# BrahMos_ESP8266.net
KiCad netlist of a schematic drawn in Altium Designer
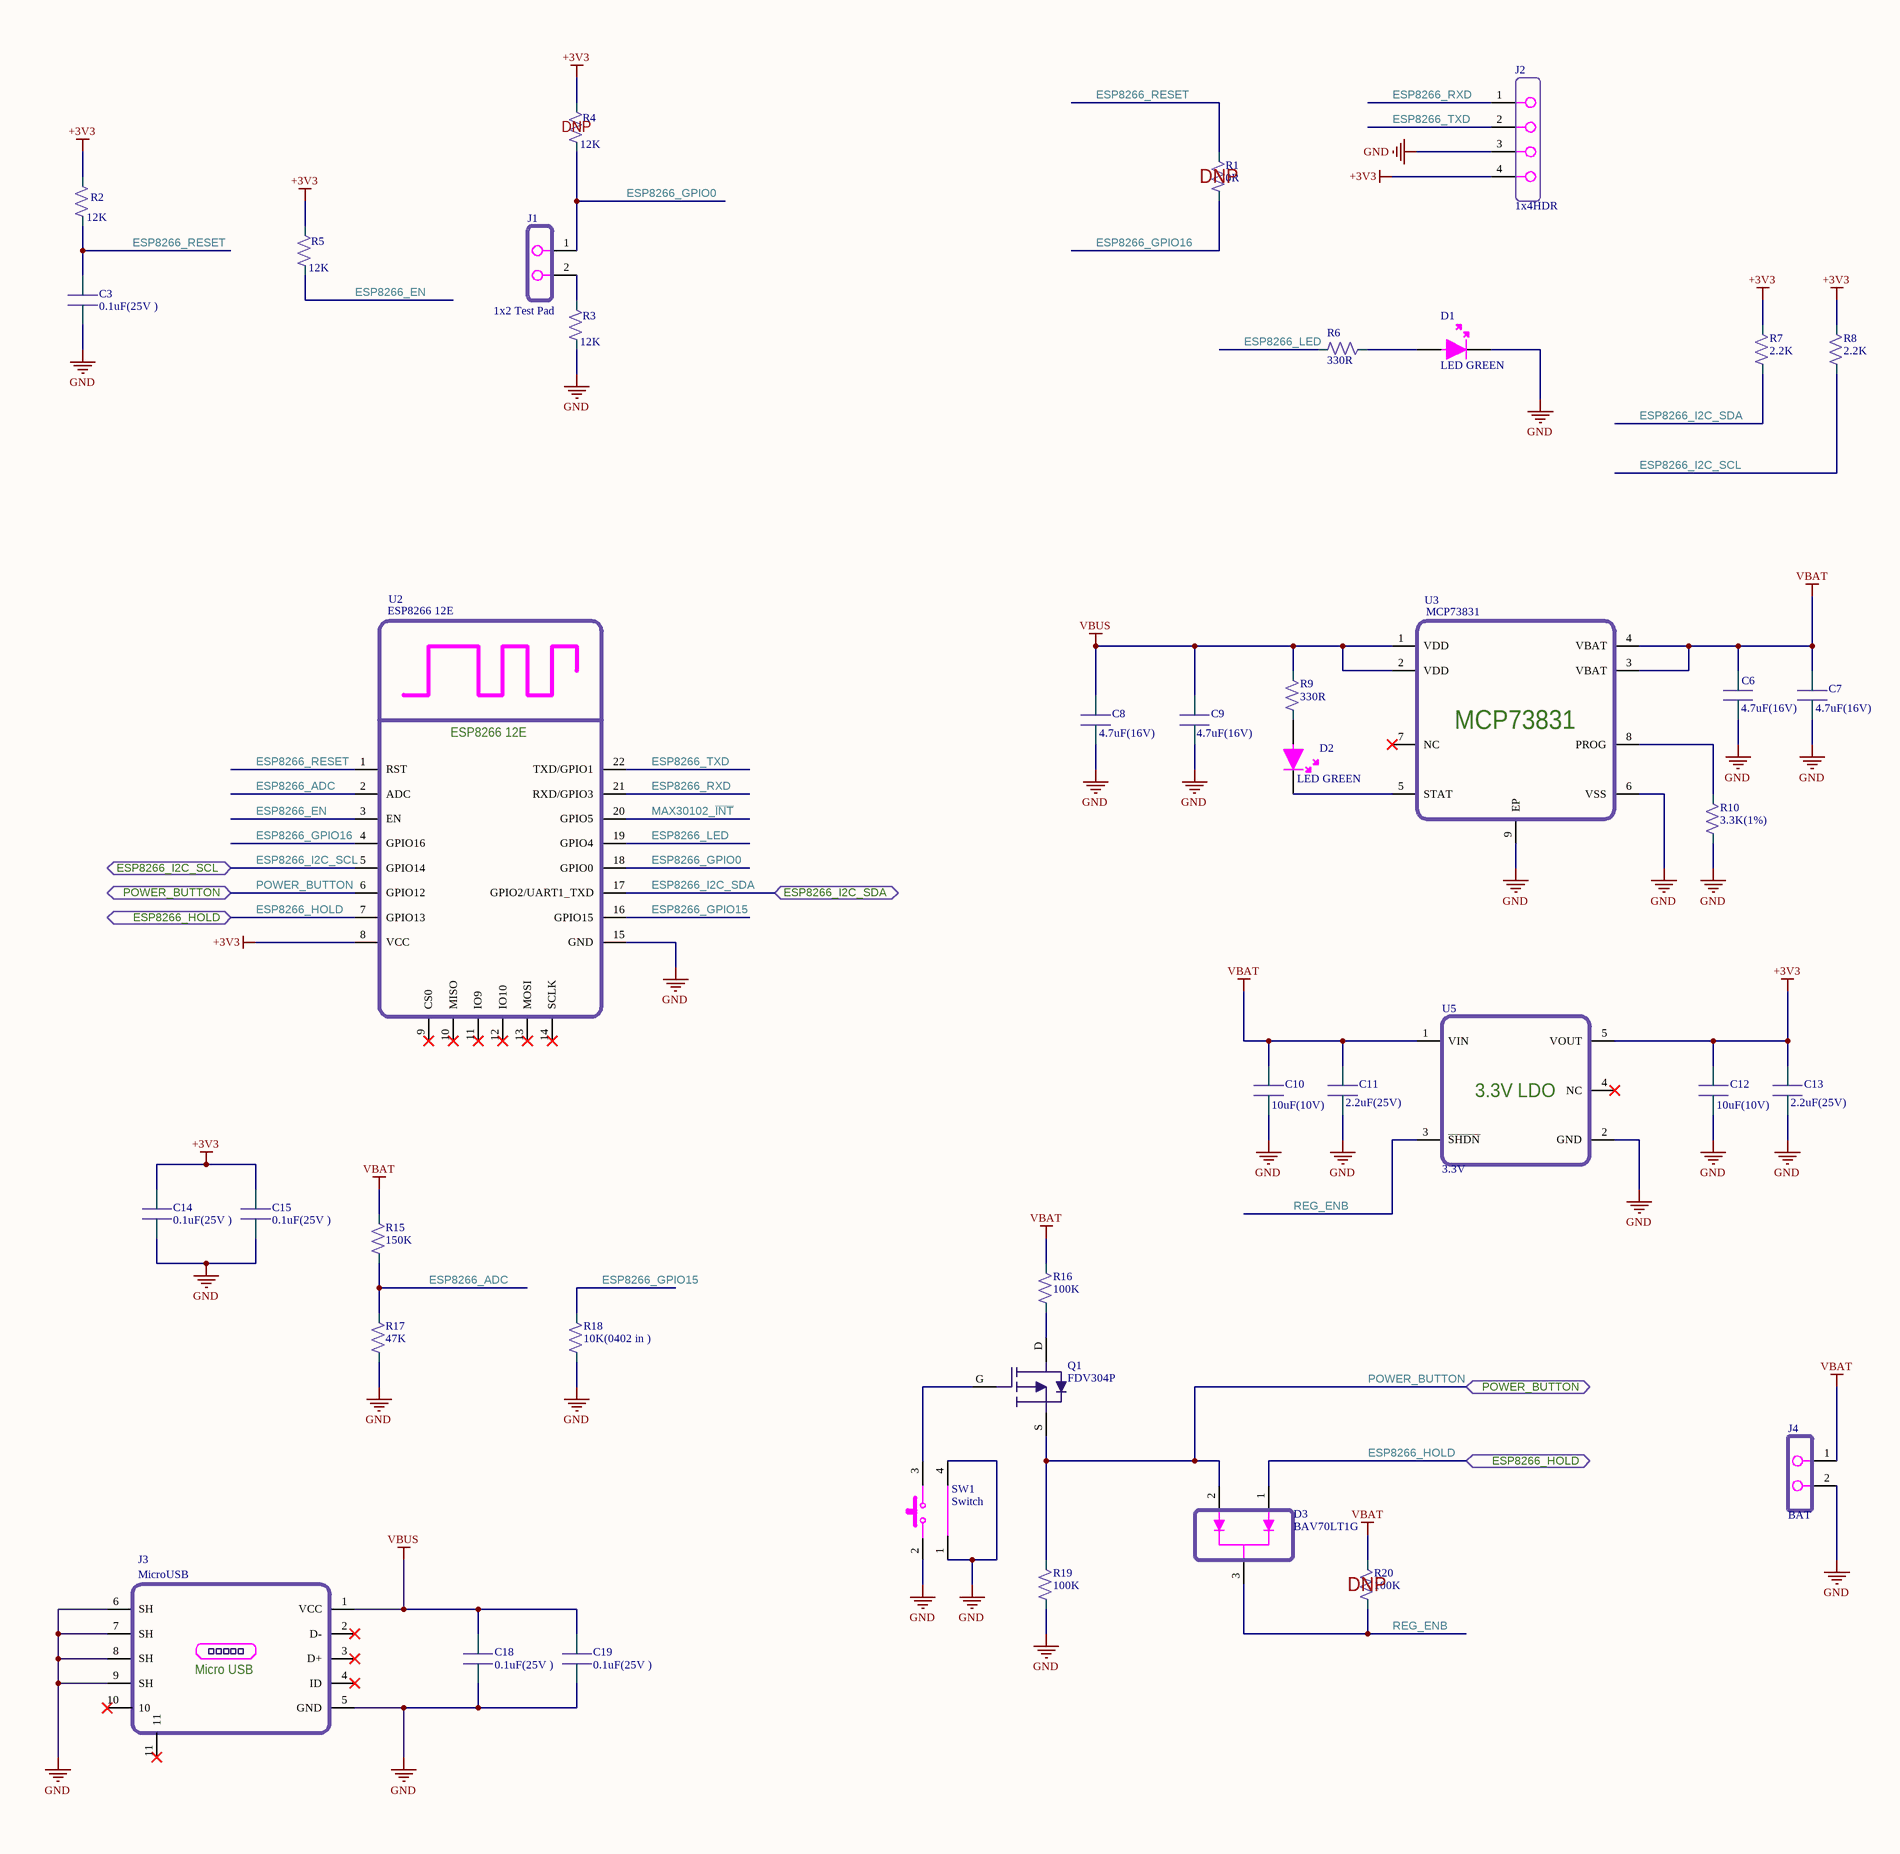
[diagram p0: BrahMos_ESP8266.SchDoc, left]
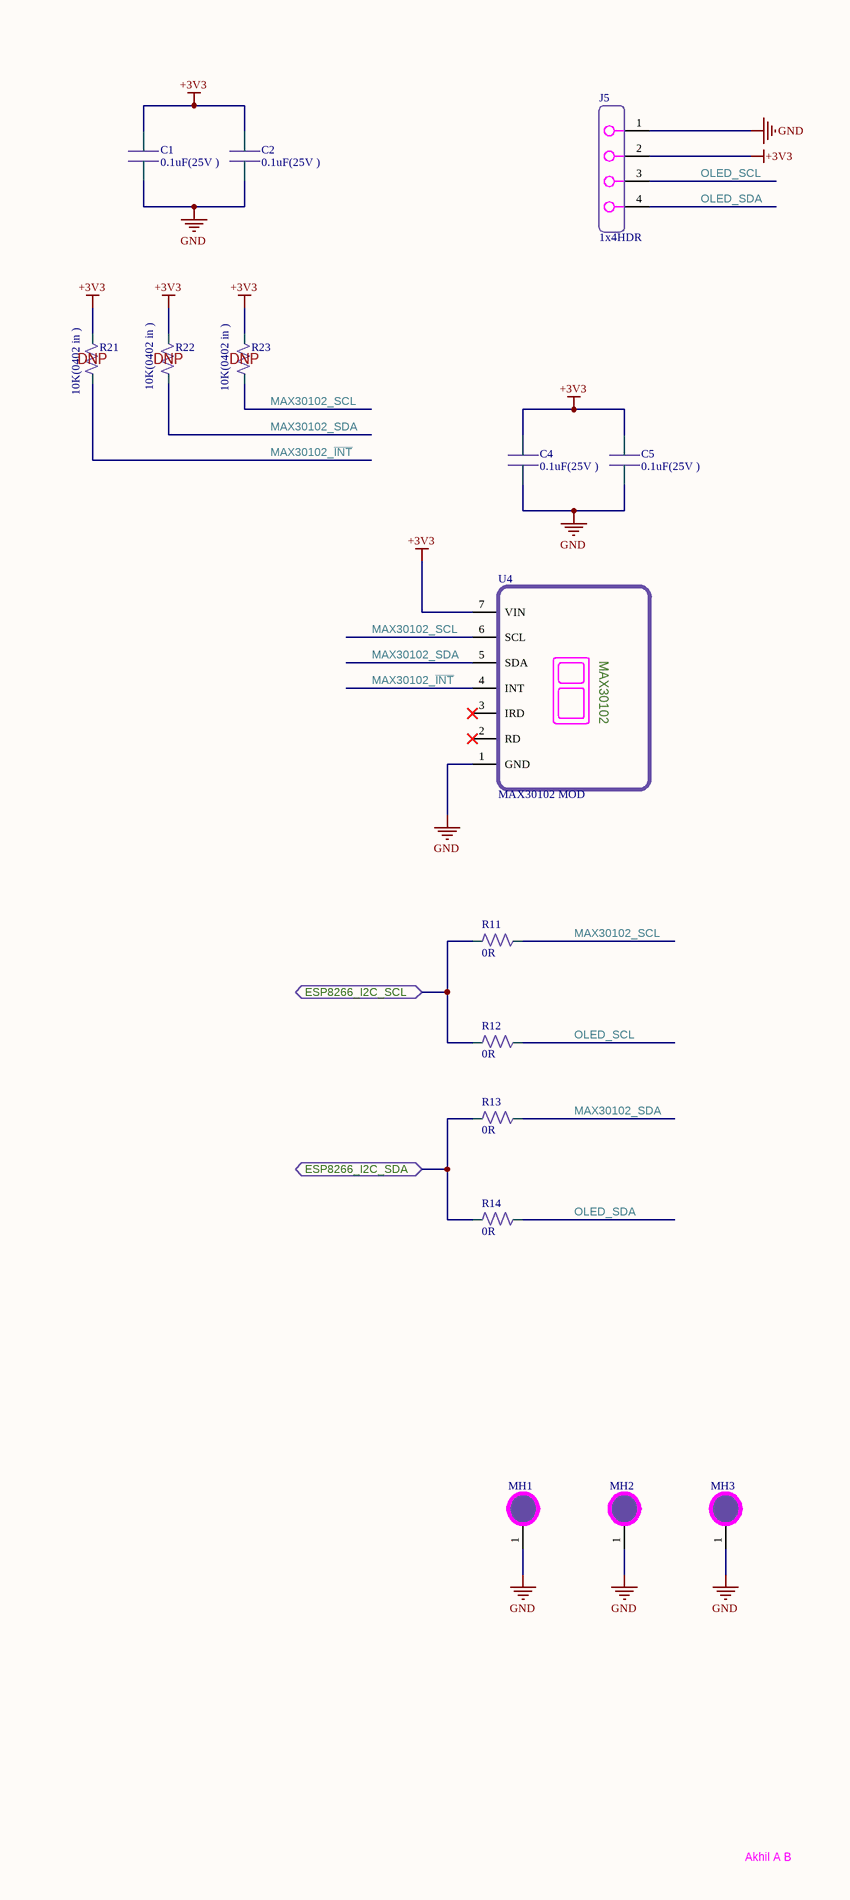
[diagram p1: BrahMos_ESP8266.SchDoc, right]

(export (version "E")
  (design (tool "Eeschema 10.0.6"))
  (components
    (comp (ref "C1")
      (value "0.1uF(25V )")
      (footprint "CAPACITOR_0402")
      (description "0.1µF ±10% 25V Ceramic Capacitor X7R 0402 (1005 Metric)")
      (fields
        (field (name "MANUFACTURERPARTNUMBER") "GRM155R71E104KE14J")
        (field (name "MANUFACTURER") "Murata Electronics")
      )
      (libsource (lib "Capacitors") (part "GRM155R71E104KE14J"))
    )
    (comp (ref "C2")
      (value "0.1uF(25V )")
      (footprint "CAPACITOR_0402")
      (description "0.1µF ±10% 25V Ceramic Capacitor X7R 0402 (1005 Metric)")
      (fields
        (field (name "MANUFACTURERPARTNUMBER") "GRM155R71E104KE14J")
        (field (name "MANUFACTURER") "Murata Electronics")
      )
      (libsource (lib "Capacitors") (part "GRM155R71E104KE14J"))
    )
    (comp (ref "C3")
      (value "0.1uF(25V )")
      (footprint "CAPACITOR_0402")
      (description "0.1µF ±10% 25V Ceramic Capacitor X7R 0402 (1005 Metric)")
      (fields
        (field (name "MANUFACTURERPARTNUMBER") "GRM155R71E104KE14J")
        (field (name "MANUFACTURER") "Murata Electronics")
      )
      (libsource (lib "Capacitors") (part "GRM155R71E104KE14J"))
    )
    (comp (ref "C4")
      (value "0.1uF(25V )")
      (footprint "CAPACITOR_0402")
      (description "0.1µF ±10% 25V Ceramic Capacitor X7R 0402 (1005 Metric)")
      (fields
        (field (name "MANUFACTURERPARTNUMBER") "GRM155R71E104KE14J")
        (field (name "MANUFACTURER") "Murata Electronics")
      )
      (libsource (lib "Capacitors") (part "GRM155R71E104KE14J"))
    )
    (comp (ref "C5")
      (value "0.1uF(25V )")
      (footprint "CAPACITOR_0402")
      (description "0.1µF ±10% 25V Ceramic Capacitor X7R 0402 (1005 Metric)")
      (fields
        (field (name "MANUFACTURERPARTNUMBER") "GRM155R71E104KE14J")
        (field (name "MANUFACTURER") "Murata Electronics")
      )
      (libsource (lib "Capacitors") (part "GRM155R71E104KE14J"))
    )
    (comp (ref "C6")
      (value "4.7uF(16V)")
      (footprint "CAPACITOR_0402")
      (description "4.7µF ±20% 16V Ceramic Capacitor X5R 0402 (1005 Metric)")
      (fields
        (field (name "MANUFACTURERPARTNUMBER") "0402YD475MAT2A")
        (field (name "MANUFACTURER") "AVX Corporation")
      )
      (libsource (lib "Capacitors") (part "0402YD475MAT2A"))
    )
    (comp (ref "C7")
      (value "4.7uF(16V)")
      (footprint "CAPACITOR_0402")
      (description "4.7µF ±20% 16V Ceramic Capacitor X5R 0402 (1005 Metric)")
      (fields
        (field (name "MANUFACTURERPARTNUMBER") "0402YD475MAT2A")
        (field (name "MANUFACTURER") "AVX Corporation")
      )
      (libsource (lib "Capacitors") (part "0402YD475MAT2A"))
    )
    (comp (ref "C8")
      (value "4.7uF(16V)")
      (footprint "CAPACITOR_0402")
      (description "4.7µF ±20% 16V Ceramic Capacitor X5R 0402 (1005 Metric)")
      (fields
        (field (name "MANUFACTURERPARTNUMBER") "0402YD475MAT2A")
        (field (name "MANUFACTURER") "AVX Corporation")
      )
      (libsource (lib "Capacitors") (part "0402YD475MAT2A"))
    )
    (comp (ref "C9")
      (value "4.7uF(16V)")
      (footprint "CAPACITOR_0402")
      (description "4.7µF ±20% 16V Ceramic Capacitor X5R 0402 (1005 Metric)")
      (fields
        (field (name "MANUFACTURERPARTNUMBER") "0402YD475MAT2A")
        (field (name "MANUFACTURER") "AVX Corporation")
      )
      (libsource (lib "Capacitors") (part "0402YD475MAT2A"))
    )
    (comp (ref "C10")
      (value "10uF(10V)")
      (footprint "CAPACITOR_0402")
      (description "10µF ±20% 10V Ceramic Capacitor X5R 0402 (1005 Metric)")
      (fields
        (field (name "MANUFACTURERPARTNUMBER") "CL05A106MP8NUB8")
        (field (name "MANUFACTURER") "Samsung Electro-Mechanics")
      )
      (libsource (lib "Capacitors") (part "CL05A106MP8NUB8"))
    )
    (comp (ref "C11")
      (value "2.2uF(25V)")
      (footprint "CAPACITOR_0402")
      (description "2.2 µF ±10% 25V Ceramic Capacitor X5R 0402 (1005 Metric)")
      (fields
        (field (name "MANUAFCTURERPARTNUMBER") "GRT155R61E225KE13D")
        (field (name "MANUFACTURER") "Murata Electronics")
      )
      (libsource (lib "Capacitors") (part "GRT155R61E225KE13D"))
    )
    (comp (ref "C12")
      (value "10uF(10V)")
      (footprint "CAPACITOR_0402")
      (description "10µF ±20% 10V Ceramic Capacitor X5R 0402 (1005 Metric)")
      (fields
        (field (name "MANUFACTURERPARTNUMBER") "CL05A106MP8NUB8")
        (field (name "MANUFACTURER") "Samsung Electro-Mechanics")
      )
      (libsource (lib "Capacitors") (part "CL05A106MP8NUB8"))
    )
    (comp (ref "C13")
      (value "2.2uF(25V)")
      (footprint "CAPACITOR_0402")
      (description "2.2 µF ±10% 25V Ceramic Capacitor X5R 0402 (1005 Metric)")
      (fields
        (field (name "MANUAFCTURERPARTNUMBER") "GRT155R61E225KE13D")
        (field (name "MANUFACTURER") "Murata Electronics")
      )
      (libsource (lib "Capacitors") (part "GRT155R61E225KE13D"))
    )
    (comp (ref "C14")
      (value "0.1uF(25V )")
      (footprint "CAPACITOR_0402")
      (description "0.1µF ±10% 25V Ceramic Capacitor X7R 0402 (1005 Metric)")
      (fields
        (field (name "MANUFACTURERPARTNUMBER") "GRM155R71E104KE14J")
        (field (name "MANUFACTURER") "Murata Electronics")
      )
      (libsource (lib "Capacitors") (part "GRM155R71E104KE14J"))
    )
    (comp (ref "C15")
      (value "0.1uF(25V )")
      (footprint "CAPACITOR_0402")
      (description "0.1µF ±10% 25V Ceramic Capacitor X7R 0402 (1005 Metric)")
      (fields
        (field (name "MANUFACTURERPARTNUMBER") "GRM155R71E104KE14J")
        (field (name "MANUFACTURER") "Murata Electronics")
      )
      (libsource (lib "Capacitors") (part "GRM155R71E104KE14J"))
    )
    (comp (ref "C18")
      (value "0.1uF(25V )")
      (footprint "CAPACITOR_0402")
      (description "0.1µF ±10% 25V Ceramic Capacitor X7R 0402 (1005 Metric)")
      (fields
        (field (name "MANUFACTURERPARTNUMBER") "GRM155R71E104KE14J")
        (field (name "MANUFACTURER") "Murata Electronics")
      )
      (libsource (lib "Capacitors") (part "GRM155R71E104KE14J"))
    )
    (comp (ref "C19")
      (value "0.1uF(25V )")
      (footprint "CAPACITOR_0402")
      (description "0.1µF ±10% 25V Ceramic Capacitor X7R 0402 (1005 Metric)")
      (fields
        (field (name "MANUFACTURERPARTNUMBER") "GRM155R71E104KE14J")
        (field (name "MANUFACTURER") "Murata Electronics")
      )
      (libsource (lib "Capacitors") (part "GRM155R71E104KE14J"))
    )
    (comp (ref "D1")
      (value "LED GREEN")
      (footprint "0603_LED")
      (description "Green 570nm LED Indication - Discrete 2.1V 0603 (1608 Metric)")
      (fields (field (name "MANUFACTURER PART NUMBER") "XZVG53W-8"))
      (libsource (lib "Diodes") (part "XZVG53W-8"))
    )
    (comp (ref "D2")
      (value "LED GREEN")
      (footprint "0603_LED")
      (description "Green 570nm LED Indication - Discrete 2.1V 0603 (1608 Metric)")
      (fields (field (name "MANUFACTURER PART NUMBER") "XZVG53W-8"))
      (libsource (lib "Diodes") (part "XZVG53W-8"))
    )
    (comp (ref "D3")
      (value "BAV70LT1G")
      (footprint "SOT-23_3LEAD - BAV70")
      (description "Diode Array 1 Pair Common Cathode Standard 200mA (DC) Surface Mount TO-236-3, SC-59, SOT-23-3")
      (fields (field (name "MANUFACTURER") "ON Semiconductor"))
      (libsource (lib "Diodes") (part "BAV70LT1G"))
    )
    (comp (ref "J1")
      (value "1x2 Test Pad")
      (footprint "dual test pad 1.27")
      (libsource (lib "connectors") (part "1x2Test Pad"))
    )
    (comp (ref "J2")
      (value "1x4HDR")
      (footprint "P2.541X4HDR")
      (description "Connector Header Through Hole 4 position 0.100\" (2.54mm)")
      (fields (field (name "MANUFACTURERPARTNUMBER") "PEC04SAAN"))
      (libsource (lib "connectors") (part "PEC04SAAN"))
    )
    (comp (ref "J3")
      (value "MicroUSB")
      (footprint "Micro USB")
      (description "USB - micro B USB 2.0 Receptacle Connector 5 Position Surface Mount, Right Angle; Through Hole")
      (fields
        (field (name "MANUFACTURERPARTNUMBER") "629105150521")
        (field (name "MANUFACTURER") "Würth Elektronik")
      )
      (libsource (lib "Connectors") (part "629105150521"))
    )
    (comp (ref "J4")
      (value "BAT")
      (footprint "SM02B-SRSS-TB(LF)(SN)")
      (description "Connector Header Surface Mount, Right Angle 2 position 0.039\" (1.00mm)")
      (fields
        (field (name "MANUFACTURERPARTNUMBER") "SM02B-SRSS-TB(LF)(SN)")
        (field (name "MANUFACTURER") "JST Sales America Inc.")
      )
      (libsource (lib "connectors") (part "SM02B-SRSS-TB(LF)(SN)"))
    )
    (comp (ref "J5")
      (value "1x4HDR")
      (footprint "P2.541X4HDR")
      (description "Connector Header Through Hole 4 position 0.100\" (2.54mm)")
      (fields (field (name "MANUFACTURERPARTNUMBER") "PEC04SAAN"))
      (libsource (lib "connectors") (part "PEC04SAAN"))
    )
    (comp (ref "MH1")
      (value "Mounting Hole")
      (footprint "2mm mounting Hole")
      (description "2mm Mounting Hole")
      (libsource (lib "connectors") (part "2mm mounting hole"))
    )
    (comp (ref "MH2")
      (value "Mounting Hole")
      (footprint "2mm mounting Hole")
      (description "2mm Mounting Hole")
      (libsource (lib "connectors") (part "2mm mounting hole"))
    )
    (comp (ref "MH3")
      (value "Mounting Hole")
      (footprint "2mm mounting Hole")
      (description "2mm Mounting Hole")
      (libsource (lib "connectors") (part "2mm mounting hole"))
    )
    (comp (ref "Q1")
      (value "FDV304P")
      (footprint "SOT-23_3LEAD")
      (description "P-Channel 460mA (Ta) 350mW (Ta) Surface Mount SOT-23")
      (fields (field (name "MANUFACTURER") "ON Semiconductor"))
      (libsource (lib "Integrated Circuits") (part "FDV304P"))
    )
    (comp (ref "R1")
      (value "0R")
      (footprint "RESISTOR_0402")
      (fields
        (field (name "MANUFACTURERPARTNUMBER") "CR0402AJ/-000GAS")
        (field (name "MANUFACTURER") "Bourns Inc.")
      )
      (libsource (lib "Resistors") (part "CR0402AJ/-000GAS"))
    )
    (comp (ref "R2")
      (value "12K")
      (footprint "RESISTOR_0402")
      (description "±5% 0.1W, 1/10W Chip Resistor 0402 (1005 Metric) Automotive AEC-Q200 Thick Film")
      (fields
        (field (name "MANUFACTURERPARTNUMBER") "ERJ-2GEJ123X")
        (field (name "MANUFACTURER") "Panasonic Electronic Components")
      )
      (libsource (lib "Resistors") (part "ERJ-2GEJ123X"))
    )
    (comp (ref "R3")
      (value "12K")
      (footprint "RESISTOR_0402")
      (description "±5% 0.1W, 1/10W Chip Resistor 0402 (1005 Metric) Automotive AEC-Q200 Thick Film")
      (fields
        (field (name "MANUFACTURERPARTNUMBER") "ERJ-2GEJ123X")
        (field (name "MANUFACTURER") "Panasonic Electronic Components")
      )
      (libsource (lib "Resistors") (part "ERJ-2GEJ123X"))
    )
    (comp (ref "R4")
      (value "12K")
      (footprint "RESISTOR_0402")
      (description "±5% 0.1W, 1/10W Chip Resistor 0402 (1005 Metric) Automotive AEC-Q200 Thick Film")
      (fields
        (field (name "MANUFACTURERPARTNUMBER") "ERJ-2GEJ123X")
        (field (name "MANUFACTURER") "Panasonic Electronic Components")
      )
      (libsource (lib "Resistors") (part "ERJ-2GEJ123X"))
    )
    (comp (ref "R5")
      (value "12K")
      (footprint "RESISTOR_0402")
      (description "±5% 0.1W, 1/10W Chip Resistor 0402 (1005 Metric) Automotive AEC-Q200 Thick Film")
      (fields
        (field (name "MANUFACTURERPARTNUMBER") "ERJ-2GEJ123X")
        (field (name "MANUFACTURER") "Panasonic Electronic Components")
      )
      (libsource (lib "Resistors") (part "ERJ-2GEJ123X"))
    )
    (comp (ref "R6")
      (value "330R")
      (footprint "RESISTOR_0402")
      (fields
        (field (name "MANUFACTURERPARTNUMBER") "CRGCQ0603J330R")
        (field (name "MANUFACTURER") "TE Connectivity Passive Product")
      )
      (libsource (lib "Resistors") (part "CRGCQ0603J330R"))
    )
    (comp (ref "R7")
      (value "2.2K")
      (footprint "RESISTOR_0402")
      (description "2.2 kOhms ±5% 0.1W, 1/10W Chip Resistor 0402 (1005 Metric) Automotive AEC-Q200 Thick Film")
      (fields
        (field (name "MANUFACTURERPARTNUMBER") "ERJ-2GEJ222X")
        (field (name "MANUFACTURER") "Panasonic Electronic Components")
      )
      (libsource (lib "Resistors") (part "ERJ-2GEJ222X"))
    )
    (comp (ref "R8")
      (value "2.2K")
      (footprint "RESISTOR_0402")
      (description "2.2 kOhms ±5% 0.1W, 1/10W Chip Resistor 0402 (1005 Metric) Automotive AEC-Q200 Thick Film")
      (fields
        (field (name "MANUFACTURERPARTNUMBER") "ERJ-2GEJ222X")
        (field (name "MANUFACTURER") "Panasonic Electronic Components")
      )
      (libsource (lib "Resistors") (part "ERJ-2GEJ222X"))
    )
    (comp (ref "R9")
      (value "330R")
      (footprint "RESISTOR_0402")
      (fields
        (field (name "MANUFACTURERPARTNUMBER") "CRGCQ0603J330R")
        (field (name "MANUFACTURER") "TE Connectivity Passive Product")
      )
      (libsource (lib "Resistors") (part "CRGCQ0603J330R"))
    )
    (comp (ref "R10")
      (value "3.3K(1%)")
      (footprint "RESISTOR_0402")
      (fields
        (field (name "MANUFACTURERPARTNUMBER") "RK73H1ETTP3301F")
        (field (name "MANUFACTURER") "KOA Speer Electronics, Inc.")
      )
      (libsource (lib "Resistors") (part "RK73H1ETTP3301F"))
    )
    (comp (ref "R11")
      (value "0R")
      (footprint "RESISTOR_0402")
      (fields
        (field (name "MANUFACTURERPARTNUMBER") "CR0402AJ/-000GAS")
        (field (name "MANUFACTURER") "Bourns Inc.")
      )
      (libsource (lib "Resistors") (part "CR0402AJ/-000GAS"))
    )
    (comp (ref "R12")
      (value "0R")
      (footprint "RESISTOR_0402")
      (fields
        (field (name "MANUFACTURERPARTNUMBER") "CR0402AJ/-000GAS")
        (field (name "MANUFACTURER") "Bourns Inc.")
      )
      (libsource (lib "Resistors") (part "CR0402AJ/-000GAS"))
    )
    (comp (ref "R13")
      (value "0R")
      (footprint "RESISTOR_0402")
      (fields
        (field (name "MANUFACTURERPARTNUMBER") "CR0402AJ/-000GAS")
        (field (name "MANUFACTURER") "Bourns Inc.")
      )
      (libsource (lib "Resistors") (part "CR0402AJ/-000GAS"))
    )
    (comp (ref "R14")
      (value "0R")
      (footprint "RESISTOR_0402")
      (fields
        (field (name "MANUFACTURERPARTNUMBER") "CR0402AJ/-000GAS")
        (field (name "MANUFACTURER") "Bourns Inc.")
      )
      (libsource (lib "Resistors") (part "CR0402AJ/-000GAS"))
    )
    (comp (ref "R15")
      (value "150K")
      (footprint "RESISTOR_0402")
      (description "150 kOhms ±5% 0.1W, 1/10W Chip Resistor 0402 (1005 Metric) Automotive AEC-Q200 Thick Film")
      (fields
        (field (name "MANUFACTURERPARTNUMBER") "ERJ-2GEJ154X")
        (field (name "MANUFACTURER") "Panasonic Electronic Components")
      )
      (libsource (lib "Resistors") (part "ERJ-2GEJ154X"))
    )
    (comp (ref "R16")
      (value "100K")
      (footprint "RESISTOR_0402")
      (description "100 kOhms ±5% 0.1W, 1/10W Chip Resistor 0402 (1005 Metric) Automotive AEC-Q200 Thick Film")
      (fields
        (field (name "MANUFACTURERPARTNUMBER") "ERJ-2GEJ104X")
        (field (name "MANUFACTURER") "Panasonic Electronic Components")
      )
      (libsource (lib "Resistors") (part "ERJ-2GEJ104X"))
    )
    (comp (ref "R17")
      (value "47K")
      (footprint "RESISTOR_0402")
      (fields
        (field (name "MANUFACTURERPARTNUMBER") "ERJ-U02J473X")
        (field (name "MANUFACTURER") "Panasonic Electronic Components")
      )
      (libsource (lib "Resistors") (part "ERJ-U02J473X"))
    )
    (comp (ref "R18")
      (value "10K(0402 in )")
      (footprint "RESISTOR_0402")
      (fields
        (field (name "MANUFACTURERPARTNUMBER") "ERJ-U02J103X")
        (field (name "MANUFACTURER") "Panasonic Electronic Components")
      )
      (libsource (lib "Resistors") (part "ERJ-U02J103X"))
    )
    (comp (ref "R19")
      (value "100K")
      (footprint "RESISTOR_0402")
      (description "100 kOhms ±5% 0.1W, 1/10W Chip Resistor 0402 (1005 Metric) Automotive AEC-Q200 Thick Film")
      (fields
        (field (name "MANUFACTURERPARTNUMBER") "ERJ-2GEJ104X")
        (field (name "MANUFACTURER") "Panasonic Electronic Components")
      )
      (libsource (lib "Resistors") (part "ERJ-2GEJ104X"))
    )
    (comp (ref "R20")
      (value "100K")
      (footprint "RESISTOR_0402")
      (description "100 kOhms ±5% 0.1W, 1/10W Chip Resistor 0402 (1005 Metric) Automotive AEC-Q200 Thick Film")
      (fields
        (field (name "MANUFACTURERPARTNUMBER") "ERJ-2GEJ104X")
        (field (name "MANUFACTURER") "Panasonic Electronic Components")
      )
      (libsource (lib "Resistors") (part "ERJ-2GEJ104X"))
    )
    (comp (ref "R21")
      (value "10K(0402 in )")
      (footprint "RESISTOR_0402")
      (fields
        (field (name "MANUFACTURERPARTNUMBER") "ERJ-U02J103X")
        (field (name "MANUFACTURER") "Panasonic Electronic Components")
      )
      (libsource (lib "Resistors") (part "ERJ-U02J103X"))
    )
    (comp (ref "R22")
      (value "10K(0402 in )")
      (footprint "RESISTOR_0402")
      (fields
        (field (name "MANUFACTURERPARTNUMBER") "ERJ-U02J103X")
        (field (name "MANUFACTURER") "Panasonic Electronic Components")
      )
      (libsource (lib "Resistors") (part "ERJ-U02J103X"))
    )
    (comp (ref "R23")
      (value "10K(0402 in )")
      (footprint "RESISTOR_0402")
      (fields
        (field (name "MANUFACTURERPARTNUMBER") "ERJ-U02J103X")
        (field (name "MANUFACTURER") "Panasonic Electronic Components")
      )
      (libsource (lib "Resistors") (part "ERJ-U02J103X"))
    )
    (comp (ref "SW1")
      (value "Switch")
      (footprint "right angle through hole switch")
      (description "Tactile Switch SPST-NO Side Actuated Through Hole, Right Angle")
      (fields
        (field (name "MANUFACTURERPARTNUMBER") "1301.9502")
        (field (name "MANUFACTURER") "Schurter Inc.")
      )
      (libsource (lib "connectors") (part "1301.9502"))
    )
    (comp (ref "U2")
      (value "ESP8266 12E")
      (footprint "ESP8266 12F")
      (libsource (lib "integrated_circuits") (part "ESP8266 12E"))
    )
    (comp (ref "U3")
      (value "MCP73831")
      (footprint "8VFDFN")
      (description "Charger IC Lithium Ion/Polymer 8-DFN (2x3)")
      (fields
        (field (name "MANUFACTURERPARTNUMBER") "MCP73831T-2DCI/MC")
        (field (name "MANUFACTURER") "Microchip Technology")
      )
      (libsource (lib "Integrated Circuits") (part "MCP73831T-2DCI/MC"))
    )
    (comp (ref "U4")
      (value "MAX30102 MOD")
      (footprint "MAX30102 MODULE")
      (libsource (lib "integrated_circuits") (part "MAX30102 MOD"))
    )
    (comp (ref "U5")
      (value "3.3V")
      (footprint "SOT23-5LEAD")
      (description "LDO Voltage Regulators Ultra Low Iq LDO")
      (fields
        (field (name "MANUAFCTURERPARTNUMBER") "MCP1812BT-033/OT")
        (field (name "MANUFACTURER") "Microchip Technology")
      )
      (libsource (lib "Integrated Circuits") (part "MCP1812BT-033/OT"))
    )
  )
  (nets
    (net (code "1") (name "+3V3") (class "Default")
      (node (ref "C1") (pin "2") (pinfunction "2_2") (pintype "passive"))
      (node (ref "C12") (pin "2") (pinfunction "2_2") (pintype "passive"))
      (node (ref "C13") (pin "2") (pinfunction "2_2") (pintype "passive"))
      (node (ref "C14") (pin "2") (pinfunction "2_2") (pintype "passive"))
      (node (ref "C15") (pin "2") (pinfunction "2_2") (pintype "passive"))
      (node (ref "C2") (pin "2") (pinfunction "2_2") (pintype "passive"))
      (node (ref "C4") (pin "2") (pinfunction "2_2") (pintype "passive"))
      (node (ref "C5") (pin "2") (pinfunction "2_2") (pintype "passive"))
      (node (ref "J2") (pin "4") (pinfunction "4_4") (pintype "passive"))
      (node (ref "J5") (pin "2") (pinfunction "2_2") (pintype "passive"))
      (node (ref "R2") (pin "2") (pinfunction "2_2") (pintype "passive"))
      (node (ref "R21") (pin "2") (pinfunction "2_2") (pintype "passive"))
      (node (ref "R22") (pin "2") (pinfunction "2_2") (pintype "passive"))
      (node (ref "R23") (pin "2") (pinfunction "2_2") (pintype "passive"))
      (node (ref "R4") (pin "2") (pinfunction "2_2") (pintype "passive"))
      (node (ref "R5") (pin "2") (pinfunction "2_2") (pintype "passive"))
      (node (ref "R7") (pin "2") (pinfunction "2_2") (pintype "passive"))
      (node (ref "R8") (pin "2") (pinfunction "2_2") (pintype "passive"))
      (node (ref "U2") (pin "8") (pinfunction "VCC_8") (pintype "passive"))
      (node (ref "U4") (pin "7") (pinfunction "VIN_7") (pintype "passive"))
      (node (ref "U5") (pin "5") (pinfunction "VOUT_5") (pintype "passive"))
    )
    (net (code "2") (name "/ESP8266_ADC") (class "Default")
      (node (ref "R15") (pin "1") (pinfunction "1_1") (pintype "passive"))
      (node (ref "R17") (pin "2") (pinfunction "2_2") (pintype "passive"))
      (node (ref "U2") (pin "2") (pinfunction "ADC_2") (pintype "passive"))
    )
    (net (code "3") (name "/ESP8266_EN") (class "Default")
      (node (ref "R5") (pin "1") (pinfunction "1_1") (pintype "passive"))
      (node (ref "U2") (pin "3") (pinfunction "EN_3") (pintype "passive"))
    )
    (net (code "4") (name "/ESP8266_GPIO0") (class "Default")
      (node (ref "J1") (pin "1") (pinfunction "1_1") (pintype "passive"))
      (node (ref "R4") (pin "1") (pinfunction "1_1") (pintype "passive"))
      (node (ref "U2") (pin "18") (pinfunction "GPIO0_18") (pintype "passive"))
    )
    (net (code "5") (name "/ESP8266_GPIO15") (class "Default")
      (node (ref "R18") (pin "2") (pinfunction "2_2") (pintype "passive"))
      (node (ref "U2") (pin "16") (pinfunction "GPIO15_16") (pintype "passive"))
    )
    (net (code "6") (name "/ESP8266_GPIO16") (class "Default")
      (node (ref "R1") (pin "1") (pinfunction "1_1") (pintype "passive"))
      (node (ref "U2") (pin "4") (pinfunction "GPIO16_4") (pintype "passive"))
    )
    (net (code "7") (name "/ESP8266_HOLD") (class "Default")
      (node (ref "D3") (pin "1") (pinfunction "1_1") (pintype "passive"))
      (node (ref "U2") (pin "7") (pinfunction "GPIO13_7") (pintype "passive"))
    )
    (net (code "8") (name "/ESP8266_I2C_SCL") (class "Default")
      (node (ref "R11") (pin "1") (pinfunction "1_1") (pintype "passive"))
      (node (ref "R12") (pin "1") (pinfunction "1_1") (pintype "passive"))
      (node (ref "R8") (pin "1") (pinfunction "1_1") (pintype "passive"))
      (node (ref "U2") (pin "5") (pinfunction "GPIO14_5") (pintype "passive"))
    )
    (net (code "9") (name "/ESP8266_I2C_SDA") (class "Default")
      (node (ref "R13") (pin "1") (pinfunction "1_1") (pintype "passive"))
      (node (ref "R14") (pin "1") (pinfunction "1_1") (pintype "passive"))
      (node (ref "R7") (pin "1") (pinfunction "1_1") (pintype "passive"))
      (node (ref "U2") (pin "17") (pinfunction "GPIO2/UART1_TXD_17") (pintype "passive"))
    )
    (net (code "10") (name "/ESP8266_LED") (class "Default")
      (node (ref "R6") (pin "1") (pinfunction "1_1") (pintype "passive"))
      (node (ref "U2") (pin "19") (pinfunction "GPIO4_19") (pintype "passive"))
    )
    (net (code "11") (name "/ESP8266_RESET") (class "Default")
      (node (ref "C3") (pin "2") (pinfunction "2_2") (pintype "passive"))
      (node (ref "R1") (pin "2") (pinfunction "2_2") (pintype "passive"))
      (node (ref "R2") (pin "1") (pinfunction "1_1") (pintype "passive"))
      (node (ref "U2") (pin "1") (pinfunction "RST_1") (pintype "passive"))
    )
    (net (code "12") (name "/ESP8266_RXD") (class "Default")
      (node (ref "J2") (pin "1") (pinfunction "1_1") (pintype "passive"))
      (node (ref "U2") (pin "21") (pinfunction "RXD/GPIO3_21") (pintype "passive"))
    )
    (net (code "13") (name "/ESP8266_TXD") (class "Default")
      (node (ref "J2") (pin "2") (pinfunction "2_2") (pintype "passive"))
      (node (ref "U2") (pin "22") (pinfunction "TXD/GPIO1_22") (pintype "passive"))
    )
    (net (code "14") (name "/MAX30102_SCL") (class "Default")
      (node (ref "R11") (pin "2") (pinfunction "2_2") (pintype "passive"))
      (node (ref "R23") (pin "1") (pinfunction "1_1") (pintype "passive"))
      (node (ref "U4") (pin "6") (pinfunction "SCL_6") (pintype "passive"))
    )
    (net (code "15") (name "/MAX30102_SDA") (class "Default")
      (node (ref "R13") (pin "2") (pinfunction "2_2") (pintype "passive"))
      (node (ref "R22") (pin "1") (pinfunction "1_1") (pintype "passive"))
      (node (ref "U4") (pin "5") (pinfunction "SDA_5") (pintype "passive"))
    )
    (net (code "16") (name "/MAX30102_~{INT}") (class "Default")
      (node (ref "R21") (pin "1") (pinfunction "1_1") (pintype "passive"))
      (node (ref "U2") (pin "20") (pinfunction "GPIO5_20") (pintype "passive"))
      (node (ref "U4") (pin "4") (pinfunction "INT_4") (pintype "passive"))
    )
    (net (code "17") (name "/OLED_SCL") (class "Default")
      (node (ref "J5") (pin "3") (pinfunction "3_3") (pintype "passive"))
      (node (ref "R12") (pin "2") (pinfunction "2_2") (pintype "passive"))
    )
    (net (code "18") (name "/OLED_SDA") (class "Default")
      (node (ref "J5") (pin "4") (pinfunction "4_4") (pintype "passive"))
      (node (ref "R14") (pin "2") (pinfunction "2_2") (pintype "passive"))
    )
    (net (code "19") (name "/POWER_BUTTON") (class "Default")
      (node (ref "D3") (pin "2") (pinfunction "2_2") (pintype "passive"))
      (node (ref "Q1") (pin "S") (pinfunction "S_S") (pintype "passive"))
      (node (ref "R19") (pin "2") (pinfunction "2_2") (pintype "passive"))
      (node (ref "U2") (pin "6") (pinfunction "GPIO12_6") (pintype "passive"))
    )
    (net (code "20") (name "/REG_ENB") (class "Default")
      (node (ref "D3") (pin "3") (pinfunction "3_3") (pintype "passive"))
      (node (ref "R20") (pin "1") (pinfunction "1_1") (pintype "passive"))
      (node (ref "U5") (pin "3") (pinfunction "~{SHDN}_3") (pintype "passive"))
    )
    (net (code "21") (name "GND") (class "Default")
      (node (ref "C1") (pin "1") (pinfunction "1_1") (pintype "passive"))
      (node (ref "C10") (pin "1") (pinfunction "1_1") (pintype "passive"))
      (node (ref "C11") (pin "1") (pinfunction "1_1") (pintype "passive"))
      (node (ref "C12") (pin "1") (pinfunction "1_1") (pintype "passive"))
      (node (ref "C13") (pin "1") (pinfunction "1_1") (pintype "passive"))
      (node (ref "C14") (pin "1") (pinfunction "1_1") (pintype "passive"))
      (node (ref "C15") (pin "1") (pinfunction "1_1") (pintype "passive"))
      (node (ref "C18") (pin "1") (pinfunction "1_1") (pintype "passive"))
      (node (ref "C19") (pin "1") (pinfunction "1_1") (pintype "passive"))
      (node (ref "C2") (pin "1") (pinfunction "1_1") (pintype "passive"))
      (node (ref "C3") (pin "1") (pinfunction "1_1") (pintype "passive"))
      (node (ref "C4") (pin "1") (pinfunction "1_1") (pintype "passive"))
      (node (ref "C5") (pin "1") (pinfunction "1_1") (pintype "passive"))
      (node (ref "C6") (pin "1") (pinfunction "1_1") (pintype "passive"))
      (node (ref "C7") (pin "1") (pinfunction "1_1") (pintype "passive"))
      (node (ref "C8") (pin "1") (pinfunction "1_1") (pintype "passive"))
      (node (ref "C9") (pin "1") (pinfunction "1_1") (pintype "passive"))
      (node (ref "D1") (pin "2") (pinfunction "2_2") (pintype "passive"))
      (node (ref "J2") (pin "3") (pinfunction "3_3") (pintype "passive"))
      (node (ref "J3") (pin "5") (pinfunction "GND_5") (pintype "passive"))
      (node (ref "J3") (pin "6") (pinfunction "SH_6") (pintype "passive"))
      (node (ref "J3") (pin "7") (pinfunction "SH_7") (pintype "passive"))
      (node (ref "J3") (pin "8") (pinfunction "SH_8") (pintype "passive"))
      (node (ref "J3") (pin "9") (pinfunction "SH_9") (pintype "passive"))
      (node (ref "J4") (pin "2") (pinfunction "2_2") (pintype "passive"))
      (node (ref "J5") (pin "1") (pinfunction "1_1") (pintype "passive"))
      (node (ref "MH1") (pin "1") (pinfunction "1_1") (pintype "passive"))
      (node (ref "MH2") (pin "1") (pinfunction "1_1") (pintype "passive"))
      (node (ref "MH3") (pin "1") (pinfunction "1_1") (pintype "passive"))
      (node (ref "R10") (pin "1") (pinfunction "1_1") (pintype "passive"))
      (node (ref "R17") (pin "1") (pinfunction "1_1") (pintype "passive"))
      (node (ref "R18") (pin "1") (pinfunction "1_1") (pintype "passive"))
      (node (ref "R19") (pin "1") (pinfunction "1_1") (pintype "passive"))
      (node (ref "R3") (pin "1") (pinfunction "1_1") (pintype "passive"))
      (node (ref "SW1") (pin "1") (pinfunction "1_1") (pintype "passive"))
      (node (ref "SW1") (pin "2") (pinfunction "2_2") (pintype "passive"))
      (node (ref "SW1") (pin "4") (pinfunction "4_4") (pintype "passive"))
      (node (ref "U2") (pin "15") (pinfunction "GND_15") (pintype "passive"))
      (node (ref "U3") (pin "6") (pinfunction "VSS_6") (pintype "passive"))
      (node (ref "U3") (pin "9") (pinfunction "EP_9") (pintype "passive"))
      (node (ref "U4") (pin "1") (pinfunction "GND_1") (pintype "passive"))
      (node (ref "U5") (pin "2") (pinfunction "GND_2") (pintype "passive"))
    )
    (net (code "22") (name "Net-(D1-Pad1)") (class "Default")
      (node (ref "D1") (pin "1") (pinfunction "1_1") (pintype "passive"))
      (node (ref "R6") (pin "2") (pinfunction "2_2") (pintype "passive"))
    )
    (net (code "23") (name "Net-(D2-Pad1)") (class "Default")
      (node (ref "D2") (pin "1") (pinfunction "1_1") (pintype "passive"))
      (node (ref "R9") (pin "1") (pinfunction "1_1") (pintype "passive"))
    )
    (net (code "24") (name "Net-(J1-Pad2)") (class "Default")
      (node (ref "J1") (pin "2") (pinfunction "2_2") (pintype "passive"))
      (node (ref "R3") (pin "2") (pinfunction "2_2") (pintype "passive"))
    )
    (net (code "25") (name "Net-(Q1-PadD)") (class "Default")
      (node (ref "Q1") (pin "D") (pinfunction "D_D") (pintype "passive"))
      (node (ref "R16") (pin "1") (pinfunction "1_1") (pintype "passive"))
    )
    (net (code "26") (name "Net-(Q1-PadG)") (class "Default")
      (node (ref "Q1") (pin "G") (pinfunction "G_G") (pintype "passive"))
      (node (ref "SW1") (pin "3") (pinfunction "3_3") (pintype "passive"))
    )
    (net (code "27") (name "Net-(U3-PROG)") (class "Default")
      (node (ref "R10") (pin "2") (pinfunction "2_2") (pintype "passive"))
      (node (ref "U3") (pin "8") (pinfunction "PROG_8") (pintype "passive"))
    )
    (net (code "28") (name "Net-(U3-STAT)") (class "Default")
      (node (ref "D2") (pin "2") (pinfunction "2_2") (pintype "passive"))
      (node (ref "U3") (pin "5") (pinfunction "STAT_5") (pintype "passive"))
    )
    (net (code "29") (name "VBAT") (class "Default")
      (node (ref "C10") (pin "2") (pinfunction "2_2") (pintype "passive"))
      (node (ref "C11") (pin "2") (pinfunction "2_2") (pintype "passive"))
      (node (ref "C6") (pin "2") (pinfunction "2_2") (pintype "passive"))
      (node (ref "C7") (pin "2") (pinfunction "2_2") (pintype "passive"))
      (node (ref "J4") (pin "1") (pinfunction "1_1") (pintype "passive"))
      (node (ref "R15") (pin "2") (pinfunction "2_2") (pintype "passive"))
      (node (ref "R16") (pin "2") (pinfunction "2_2") (pintype "passive"))
      (node (ref "R20") (pin "2") (pinfunction "2_2") (pintype "passive"))
      (node (ref "U3") (pin "3") (pinfunction "VBAT_3") (pintype "passive"))
      (node (ref "U3") (pin "4") (pinfunction "VBAT_4") (pintype "passive"))
      (node (ref "U5") (pin "1") (pinfunction "VIN_1") (pintype "passive"))
    )
    (net (code "30") (name "VBUS") (class "Default")
      (node (ref "C18") (pin "2") (pinfunction "2_2") (pintype "passive"))
      (node (ref "C19") (pin "2") (pinfunction "2_2") (pintype "passive"))
      (node (ref "C8") (pin "2") (pinfunction "2_2") (pintype "passive"))
      (node (ref "C9") (pin "2") (pinfunction "2_2") (pintype "passive"))
      (node (ref "J3") (pin "1") (pinfunction "VCC_1") (pintype "passive"))
      (node (ref "R9") (pin "2") (pinfunction "2_2") (pintype "passive"))
      (node (ref "U3") (pin "1") (pinfunction "VDD_1") (pintype "passive"))
      (node (ref "U3") (pin "2") (pinfunction "VDD_2") (pintype "passive"))
    )
    (net (code "31") (name "unconnected-(J3-D+-Pad3)") (class "Default")
      (node (ref "J3") (pin "3") (pinfunction "D+_3") (pintype "passive+no_connect"))
    )
    (net (code "32") (name "unconnected-(J3-D--Pad2)") (class "Default")
      (node (ref "J3") (pin "2") (pinfunction "D-_2") (pintype "passive+no_connect"))
    )
    (net (code "33") (name "unconnected-(J3-ID-Pad4)") (class "Default")
      (node (ref "J3") (pin "4") (pinfunction "ID_4") (pintype "passive+no_connect"))
    )
    (net (code "34") (name "unconnected-(J3-Pad10)") (class "Default")
      (node (ref "J3") (pin "10") (pinfunction "10_10") (pintype "passive+no_connect"))
    )
    (net (code "35") (name "unconnected-(J3-Pad11)") (class "Default")
      (node (ref "J3") (pin "11") (pinfunction "11_11") (pintype "passive+no_connect"))
    )
    (net (code "36") (name "unconnected-(U2-CS0-Pad9)") (class "Default")
      (node (ref "U2") (pin "9") (pinfunction "CS0_9") (pintype "passive+no_connect"))
    )
    (net (code "37") (name "unconnected-(U2-IO9-Pad11)") (class "Default")
      (node (ref "U2") (pin "11") (pinfunction "IO9_11") (pintype "passive+no_connect"))
    )
    (net (code "38") (name "unconnected-(U2-IO10-Pad12)") (class "Default")
      (node (ref "U2") (pin "12") (pinfunction "IO10_12") (pintype "passive+no_connect"))
    )
    (net (code "39") (name "unconnected-(U2-MISO-Pad10)") (class "Default")
      (node (ref "U2") (pin "10") (pinfunction "MISO_10") (pintype "passive+no_connect"))
    )
    (net (code "40") (name "unconnected-(U2-MOSI-Pad13)") (class "Default")
      (node (ref "U2") (pin "13") (pinfunction "MOSI_13") (pintype "passive+no_connect"))
    )
    (net (code "41") (name "unconnected-(U2-SCLK-Pad14)") (class "Default")
      (node (ref "U2") (pin "14") (pinfunction "SCLK_14") (pintype "passive+no_connect"))
    )
    (net (code "42") (name "unconnected-(U3-NC-Pad7)") (class "Default")
      (node (ref "U3") (pin "7") (pinfunction "NC_7") (pintype "passive+no_connect"))
    )
    (net (code "43") (name "unconnected-(U4-IRD-Pad3)") (class "Default")
      (node (ref "U4") (pin "3") (pinfunction "IRD_3") (pintype "passive+no_connect"))
    )
    (net (code "44") (name "unconnected-(U4-RD-Pad2)") (class "Default")
      (node (ref "U4") (pin "2") (pinfunction "RD_2") (pintype "passive+no_connect"))
    )
    (net (code "45") (name "unconnected-(U5-NC-Pad4)") (class "Default")
      (node (ref "U5") (pin "4") (pinfunction "NC_4") (pintype "passive+no_connect"))
    )
  )
)
